# Schematic.net
KiCad netlist of a schematic drawn in Altium Designer
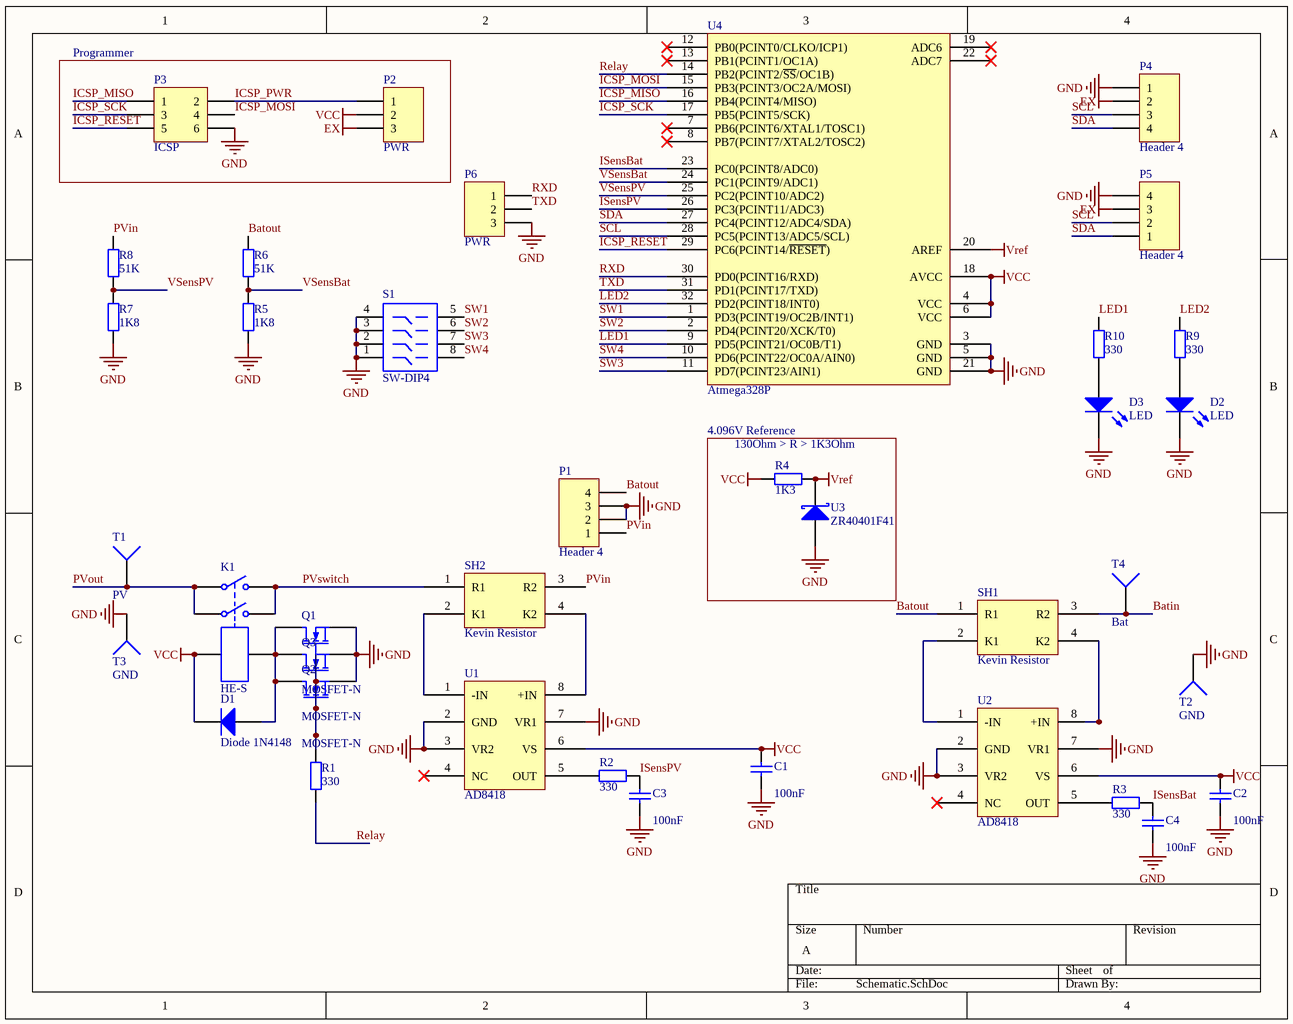
[diagram p0: Schematic.SchDoc]

(export (version "E")
  (design (tool "Eeschema 10.0.6"))
  (components
    (comp (ref "C1")
      (value "100nF")
      (footprint "CAP 0805/2012")
      (description "Capacitor")
      (fields (field (name "Comment") "Cap") (field (name "PUBLISHER") "Altium Limited"))
      (libsource (lib "Miscellaneous Devices") (part "Cap"))
    )
    (comp (ref "C2")
      (value "100nF")
      (footprint "CAP 0805/2012")
      (description "Capacitor")
      (fields (field (name "Comment") "Cap") (field (name "PUBLISHER") "Altium Limited"))
      (libsource (lib "Miscellaneous Devices") (part "Cap"))
    )
    (comp (ref "C3")
      (value "100nF")
      (footprint "CAP 0805/2012")
      (description "Capacitor")
      (fields (field (name "Comment") "Cap") (field (name "PUBLISHER") "Altium Limited"))
      (libsource (lib "Miscellaneous Devices") (part "Cap"))
    )
    (comp (ref "C4")
      (value "100nF")
      (footprint "CAP 0805/2012")
      (description "Capacitor")
      (fields (field (name "Comment") "Cap") (field (name "PUBLISHER") "Altium Limited"))
      (libsource (lib "Miscellaneous Devices") (part "Cap"))
    )
    (comp (ref "D1")
      (value "Diode 1N4148")
      (footprint "DO-35")
      (description "High Conductance Fast Diode")
      (fields (field (name "PUBLISHER") "Altium Limited"))
      (libsource (lib "Miscellaneous Devices") (part "Diode 1N4148"))
    )
    (comp (ref "D2")
      (value "LED")
      (footprint "LED 0805/2012 RED")
      (description "Typical INFRARED GaAs LED")
      (fields (field (name "PUBLISHER") "Altium Limited"))
      (libsource (lib "Miscellaneous Devices") (part "LED0"))
    )
    (comp (ref "D3")
      (value "LED")
      (footprint "LED 0805/2012 RED")
      (description "Typical INFRARED GaAs LED")
      (fields (field (name "PUBLISHER") "Altium Limited"))
      (libsource (lib "Miscellaneous Devices") (part "LED0"))
    )
    (comp (ref "K1")
      (value "HE-S")
      (footprint "Relay HE-S Parasonic")
      (description "Dual-Pole Single-Throw Relay")
      (fields (field (name "PUBLISHER") "Altium Limited"))
      (libsource (lib "Miscellaneous Devices") (part "Relay-DPST"))
    )
    (comp (ref "P1")
      (value "Header 4")
      (footprint "4Pin 6.35mm Connector")
      (description "Header, 4-Pin")
      (fields (field (name "PUBLISHER") "Altium Limited"))
      (libsource (lib "") (part "Header 4_2"))
    )
    (comp (ref "P2")
      (value "PWR")
      (footprint "HDR1X3")
      (description "Header, 3-Pin")
      (fields (field (name "PUBLISHER") "Altium Limited"))
      (libsource (lib "Miscellaneous Connectors") (part "Header 3"))
    )
    (comp (ref "P3")
      (value "ICSP")
      (footprint "HDR2X3")
      (description "Header, 3-Pin, Dual row")
      (fields (field (name "PUBLISHER") "Altium Limited"))
      (libsource (lib "Miscellaneous Connectors") (part "Header 3X2"))
    )
    (comp (ref "P4")
      (value "Header 4")
      (footprint "TE 282834-4")
      (description "Header, 4-Pin")
      (fields (field (name "PUBLISHER") "Altium Limited"))
      (libsource (lib "Miscellaneous Connectors") (part "Header 4"))
    )
    (comp (ref "P5")
      (value "Header 4")
      (footprint "TE 282834-4")
      (description "Header, 4-Pin")
      (fields (field (name "PUBLISHER") "Altium Limited"))
      (libsource (lib "") (part "Header 4_1"))
    )
    (comp (ref "P6")
      (value "PWR")
      (footprint "HDR1X3H")
      (description "Header, 3-Pin")
      (fields (field (name "PUBLISHER") "Altium Limited"))
      (libsource (lib "") (part "Header 3_1"))
    )
    (comp (ref "Q1")
      (value "MOSFET-N")
      (footprint "DIODES SOT-23-3")
      (description "N-Channel MOSFET")
      (fields (field (name "PUBLISHER") "Altium Limited"))
      (libsource (lib "Miscellaneous Devices") (part "MOSFET-N"))
    )
    (comp (ref "Q2")
      (value "MOSFET-N")
      (footprint "DIODES SOT-23-3")
      (description "N-Channel MOSFET")
      (fields (field (name "PUBLISHER") "Altium Limited"))
      (libsource (lib "Miscellaneous Devices") (part "MOSFET-N"))
    )
    (comp (ref "Q3")
      (value "MOSFET-N")
      (footprint "DIODES SOT-23-3")
      (description "N-Channel MOSFET")
      (fields (field (name "PUBLISHER") "Altium Limited"))
      (libsource (lib "Miscellaneous Devices") (part "MOSFET-N"))
    )
    (comp (ref "R1")
      (value "330")
      (footprint "RES 0805/2012")
      (description "Resistor")
      (fields (field (name "Comment") "Res2") (field (name "PUBLISHER") "Altium Limited"))
      (libsource (lib "") (part "Res2_2"))
    )
    (comp (ref "R2")
      (value "330")
      (footprint "RES 0805/2012")
      (description "Resistor")
      (fields (field (name "Comment") "Res2") (field (name "PUBLISHER") "Altium Limited"))
      (libsource (lib "Miscellaneous Devices") (part "Res2"))
    )
    (comp (ref "R3")
      (value "330")
      (footprint "RES 0805/2012")
      (description "Resistor")
      (fields (field (name "Comment") "Res2") (field (name "PUBLISHER") "Altium Limited"))
      (libsource (lib "Miscellaneous Devices") (part "Res2"))
    )
    (comp (ref "R4")
      (value "1K3")
      (footprint "RES 0805/2012")
      (description "Resistor")
      (fields (field (name "Comment") "Res2") (field (name "PUBLISHER") "Altium Limited"))
      (libsource (lib "Miscellaneous Devices") (part "Res2"))
    )
    (comp (ref "R5")
      (value "1K8")
      (footprint "RES 0805/2012")
      (description "Resistor")
      (fields (field (name "Comment") "Res2") (field (name "PUBLISHER") "Altium Limited"))
      (libsource (lib "") (part "Res2_1"))
    )
    (comp (ref "R6")
      (value "51K")
      (footprint "RES 0805/2012")
      (description "Resistor")
      (fields (field (name "Comment") "Res2") (field (name "PUBLISHER") "Altium Limited"))
      (libsource (lib "") (part "Res2_1"))
    )
    (comp (ref "R7")
      (value "1K8")
      (footprint "RES 0805/2012")
      (description "Resistor")
      (fields (field (name "Comment") "Res2") (field (name "PUBLISHER") "Altium Limited"))
      (libsource (lib "") (part "Res2_1"))
    )
    (comp (ref "R8")
      (value "51K")
      (footprint "RES 0805/2012")
      (description "Resistor")
      (fields (field (name "Comment") "Res2") (field (name "PUBLISHER") "Altium Limited"))
      (libsource (lib "") (part "Res2_1"))
    )
    (comp (ref "R9")
      (value "330")
      (footprint "RES 0805/2012")
      (description "Resistor")
      (fields (field (name "Comment") "Res2") (field (name "PUBLISHER") "Altium Limited"))
      (libsource (lib "") (part "Res2_1"))
    )
    (comp (ref "R10")
      (value "330")
      (footprint "RES 0805/2012")
      (description "Resistor")
      (fields (field (name "Comment") "Res2") (field (name "PUBLISHER") "Altium Limited"))
      (libsource (lib "") (part "Res2_1"))
    )
    (comp (ref "S1")
      (value "SW-DIP4")
      (footprint "DIP-8")
      (description "DIP Switch")
      (fields (field (name "PUBLISHER") "Altium Limited"))
      (libsource (lib "Miscellaneous Devices") (part "SW-DIP4"))
    )
    (comp (ref "SH1")
      (value "Kevin Resistor")
      (footprint "TE TLR Shunt")
      (libsource (lib "Personal Library") (part "Kevin Resistor"))
    )
    (comp (ref "SH2")
      (value "Kevin Resistor")
      (footprint "TE TLR Shunt")
      (libsource (lib "Personal Library") (part "Kevin Resistor"))
    )
    (comp (ref "T1")
      (value "PV")
      (footprint "PCB_Pin_Outsteeksel")
      (description "Socket")
      (fields (field (name "PUBLISHER") "Altium Limited"))
      (libsource (lib "Miscellaneous Connectors") (part "Socket"))
    )
    (comp (ref "T2")
      (value "GND")
      (footprint "PCB_Pin_Outsteeksel")
      (description "Socket")
      (fields (field (name "PUBLISHER") "Altium Limited"))
      (libsource (lib "Miscellaneous Connectors") (part "Socket"))
    )
    (comp (ref "T3")
      (value "GND")
      (footprint "PCB_Pin_Outsteeksel")
      (description "Socket")
      (fields (field (name "PUBLISHER") "Altium Limited"))
      (libsource (lib "Miscellaneous Connectors") (part "Socket"))
    )
    (comp (ref "T4")
      (value "Bat")
      (footprint "PCB_Pin_Outsteeksel")
      (description "Socket")
      (fields (field (name "PUBLISHER") "Altium Limited"))
      (libsource (lib "Miscellaneous Connectors") (part "Socket"))
    )
    (comp (ref "U1")
      (value "AD8418")
      (footprint "INTERSIL MSOP-8 M8.118")
      (libsource (lib "GJ24") (part "AD8418"))
    )
    (comp (ref "U2")
      (value "AD8418")
      (footprint "INTERSIL MSOP-8 M8.118")
      (libsource (lib "GJ24") (part "AD8418"))
    )
    (comp (ref "U3")
      (value "ZR40401F41")
      (footprint "DIODES SOT-23-3")
      (description "Schottky Rectifier")
      (fields (field (name "PUBLISHER") "Altium Limited"))
      (libsource (lib "Miscellaneous Devices") (part "Diode 10TQ035"))
    )
    (comp (ref "U4")
      (value "Atmega328P")
      (footprint "ST LQFP-32 7X7MM")
      (libsource (lib "GJ24") (part "Atmega328P"))
    )
  )
  (nets
    (net (code "1") (name "/Batin") (class "Default")
      (node (ref "SH1") (pin "3") (pinfunction "R2_3") (pintype "passive"))
      (node (ref "T4") (pin "1") (pinfunction "1_1") (pintype "passive"))
    )
    (net (code "2") (name "/Batout") (class "Default")
      (node (ref "P1") (pin "4") (pinfunction "4_4") (pintype "passive"))
      (node (ref "R6") (pin "2") (pinfunction "2_2") (pintype "passive"))
      (node (ref "SH1") (pin "1") (pinfunction "R1_1") (pintype "passive"))
    )
    (net (code "3") (name "/ICSP_MISO") (class "Default")
      (node (ref "P3") (pin "1") (pinfunction "1_1") (pintype "passive"))
      (node (ref "U4") (pin "16") (pinfunction "PB4(PCINT4/MISO)_16") (pintype "passive"))
    )
    (net (code "4") (name "/ICSP_MOSI") (class "Default")
      (node (ref "P3") (pin "4") (pinfunction "4_4") (pintype "passive"))
      (node (ref "U4") (pin "15") (pinfunction "PB3(PCINT3/OC2A/MOSI)_15") (pintype "passive"))
    )
    (net (code "5") (name "/ICSP_PWR") (class "Default")
      (node (ref "P2") (pin "1") (pinfunction "1_1") (pintype "passive"))
      (node (ref "P3") (pin "2") (pinfunction "2_2") (pintype "passive"))
    )
    (net (code "6") (name "/ICSP_RESET") (class "Default")
      (node (ref "P3") (pin "5") (pinfunction "5_5") (pintype "passive"))
      (node (ref "U4") (pin "29") (pinfunction "PC6(PCINT14/~{RESET})_29") (pintype "passive"))
    )
    (net (code "7") (name "/ICSP_SCK") (class "Default")
      (node (ref "P3") (pin "3") (pinfunction "3_3") (pintype "passive"))
      (node (ref "U4") (pin "17") (pinfunction "PB5(PCINT5/SCK)_17") (pintype "passive"))
    )
    (net (code "8") (name "/ISensBat") (class "Default")
      (node (ref "C4") (pin "2") (pinfunction "2_2") (pintype "passive"))
      (node (ref "R3") (pin "1") (pinfunction "1_1") (pintype "passive"))
      (node (ref "U4") (pin "23") (pinfunction "PC0(PCINT8/ADC0)_23") (pintype "passive"))
    )
    (net (code "9") (name "/ISensPV") (class "Default")
      (node (ref "C3") (pin "2") (pinfunction "2_2") (pintype "passive"))
      (node (ref "R2") (pin "1") (pinfunction "1_1") (pintype "passive"))
      (node (ref "U4") (pin "26") (pinfunction "PC3(PCINT11/ADC3)_26") (pintype "passive"))
    )
    (net (code "10") (name "/LED1") (class "Default")
      (node (ref "R10") (pin "2") (pinfunction "2_2") (pintype "passive"))
      (node (ref "U4") (pin "9") (pinfunction "PD5(PCINT21/OC0B/T1)_9") (pintype "passive"))
    )
    (net (code "11") (name "/LED2") (class "Default")
      (node (ref "R9") (pin "2") (pinfunction "2_2") (pintype "passive"))
      (node (ref "U4") (pin "32") (pinfunction "PD2(PCINT18/INT0)_32") (pintype "passive"))
    )
    (net (code "12") (name "/PVin") (class "Default")
      (node (ref "P1") (pin "1") (pinfunction "1_1") (pintype "passive"))
      (node (ref "R8") (pin "2") (pinfunction "2_2") (pintype "passive"))
      (node (ref "SH2") (pin "3") (pinfunction "R2_3") (pintype "passive"))
    )
    (net (code "13") (name "/PVout") (class "Default")
      (node (ref "K1") (pin "1") (pinfunction "1_1") (pintype "passive"))
      (node (ref "K1") (pin "3") (pinfunction "3_3") (pintype "passive"))
      (node (ref "T1") (pin "1") (pinfunction "1_1") (pintype "passive"))
    )
    (net (code "14") (name "/PVswitch") (class "Default")
      (node (ref "K1") (pin "2") (pinfunction "2_2") (pintype "passive"))
      (node (ref "K1") (pin "4") (pinfunction "4_4") (pintype "passive"))
      (node (ref "SH2") (pin "1") (pinfunction "R1_1") (pintype "passive"))
    )
    (net (code "15") (name "/RXD") (class "Default")
      (node (ref "P6") (pin "1") (pinfunction "1_1") (pintype "passive"))
      (node (ref "U4") (pin "30") (pinfunction "PD0(PCINT16/RXD)_30") (pintype "passive"))
    )
    (net (code "16") (name "/Relay") (class "Default")
      (node (ref "R1") (pin "2") (pinfunction "2_2") (pintype "passive"))
      (node (ref "U4") (pin "14") (pinfunction "PB2(PCINT2/~{SS}/OC1B)_14") (pintype "passive"))
    )
    (net (code "17") (name "/SCL") (class "Default")
      (node (ref "P4") (pin "3") (pinfunction "3_3") (pintype "passive"))
      (node (ref "P5") (pin "2") (pinfunction "2_2") (pintype "passive"))
      (node (ref "U4") (pin "28") (pinfunction "PC5(PCINT13/ADC5/SCL)_28") (pintype "passive"))
    )
    (net (code "18") (name "/SDA") (class "Default")
      (node (ref "P4") (pin "4") (pinfunction "4_4") (pintype "passive"))
      (node (ref "P5") (pin "1") (pinfunction "1_1") (pintype "passive"))
      (node (ref "U4") (pin "27") (pinfunction "PC4(PCINT12/ADC4/SDA)_27") (pintype "passive"))
    )
    (net (code "19") (name "/SW1") (class "Default")
      (node (ref "S1") (pin "5") (pinfunction "5_5") (pintype "passive"))
      (node (ref "U4") (pin "1") (pinfunction "PD3(PCINT19/OC2B/INT1)_1") (pintype "passive"))
    )
    (net (code "20") (name "/SW2") (class "Default")
      (node (ref "S1") (pin "6") (pinfunction "6_6") (pintype "passive"))
      (node (ref "U4") (pin "2") (pinfunction "PD4(PCINT20/XCK/T0)_2") (pintype "passive"))
    )
    (net (code "21") (name "/SW3") (class "Default")
      (node (ref "S1") (pin "7") (pinfunction "7_7") (pintype "passive"))
      (node (ref "U4") (pin "11") (pinfunction "PD7(PCINT23/AIN1)_11") (pintype "passive"))
    )
    (net (code "22") (name "/SW4") (class "Default")
      (node (ref "S1") (pin "8") (pinfunction "8_8") (pintype "passive"))
      (node (ref "U4") (pin "10") (pinfunction "PD6(PCINT22/OC0A/AIN0)_10") (pintype "passive"))
    )
    (net (code "23") (name "/TXD") (class "Default")
      (node (ref "P6") (pin "2") (pinfunction "2_2") (pintype "passive"))
      (node (ref "U4") (pin "31") (pinfunction "PD1(PCINT17/TXD)_31") (pintype "passive"))
    )
    (net (code "24") (name "/VSensBat") (class "Default")
      (node (ref "R5") (pin "2") (pinfunction "2_2") (pintype "passive"))
      (node (ref "R6") (pin "1") (pinfunction "1_1") (pintype "passive"))
      (node (ref "U4") (pin "24") (pinfunction "PC1(PCINT9/ADC1)_24") (pintype "passive"))
    )
    (net (code "25") (name "/VSensPV") (class "Default")
      (node (ref "R7") (pin "2") (pinfunction "2_2") (pintype "passive"))
      (node (ref "R8") (pin "1") (pinfunction "1_1") (pintype "passive"))
      (node (ref "U4") (pin "25") (pinfunction "PC2(PCINT10/ADC2)_25") (pintype "passive"))
    )
    (net (code "26") (name "EX") (class "Default")
      (node (ref "P2") (pin "3") (pinfunction "3_3") (pintype "passive"))
      (node (ref "P4") (pin "2") (pinfunction "2_2") (pintype "passive"))
      (node (ref "P5") (pin "3") (pinfunction "3_3") (pintype "passive"))
    )
    (net (code "27") (name "GND") (class "Default")
      (node (ref "C1") (pin "1") (pinfunction "1_1") (pintype "passive"))
      (node (ref "C2") (pin "1") (pinfunction "1_1") (pintype "passive"))
      (node (ref "C3") (pin "1") (pinfunction "1_1") (pintype "passive"))
      (node (ref "C4") (pin "1") (pinfunction "1_1") (pintype "passive"))
      (node (ref "D2") (pin "2") (pinfunction "K_2") (pintype "passive"))
      (node (ref "D3") (pin "2") (pinfunction "K_2") (pintype "passive"))
      (node (ref "P1") (pin "2") (pinfunction "2_2") (pintype "passive"))
      (node (ref "P1") (pin "3") (pinfunction "3_3") (pintype "passive"))
      (node (ref "P3") (pin "6") (pinfunction "6_6") (pintype "passive"))
      (node (ref "P4") (pin "1") (pinfunction "1_1") (pintype "passive"))
      (node (ref "P5") (pin "4") (pinfunction "4_4") (pintype "passive"))
      (node (ref "P6") (pin "3") (pinfunction "3_3") (pintype "passive"))
      (node (ref "Q1") (pin "2") (pinfunction "S_2") (pintype "passive"))
      (node (ref "Q2") (pin "2") (pinfunction "S_2") (pintype "passive"))
      (node (ref "Q3") (pin "2") (pinfunction "S_2") (pintype "passive"))
      (node (ref "R5") (pin "1") (pinfunction "1_1") (pintype "passive"))
      (node (ref "R7") (pin "1") (pinfunction "1_1") (pintype "passive"))
      (node (ref "S1") (pin "1") (pinfunction "1_1") (pintype "passive"))
      (node (ref "S1") (pin "2") (pinfunction "2_2") (pintype "passive"))
      (node (ref "S1") (pin "3") (pinfunction "3_3") (pintype "passive"))
      (node (ref "S1") (pin "4") (pinfunction "4_4") (pintype "passive"))
      (node (ref "T2") (pin "1") (pinfunction "1_1") (pintype "passive"))
      (node (ref "T3") (pin "1") (pinfunction "1_1") (pintype "passive"))
      (node (ref "U1") (pin "2") (pinfunction "GND_2") (pintype "passive"))
      (node (ref "U1") (pin "3") (pinfunction "VR2_3") (pintype "passive"))
      (node (ref "U1") (pin "7") (pinfunction "VR1_7") (pintype "passive"))
      (node (ref "U2") (pin "2") (pinfunction "GND_2") (pintype "passive"))
      (node (ref "U2") (pin "3") (pinfunction "VR2_3") (pintype "passive"))
      (node (ref "U2") (pin "7") (pinfunction "VR1_7") (pintype "passive"))
      (node (ref "U3") (pin "3") (pinfunction "A_3") (pintype "passive"))
      (node (ref "U4") (pin "21") (pinfunction "GND_21") (pintype "passive"))
      (node (ref "U4") (pin "3") (pinfunction "GND_3") (pintype "passive"))
      (node (ref "U4") (pin "5") (pinfunction "GND_5") (pintype "passive"))
    )
    (net (code "28") (name "Net-(D1-A)") (class "Default")
      (node (ref "D1") (pin "1") (pinfunction "A_1") (pintype "passive"))
      (node (ref "K1") (pin "6") (pinfunction "6_6") (pintype "passive"))
      (node (ref "Q1") (pin "1") (pinfunction "D_1") (pintype "passive"))
      (node (ref "Q2") (pin "1") (pinfunction "D_1") (pintype "passive"))
      (node (ref "Q3") (pin "1") (pinfunction "D_1") (pintype "passive"))
    )
    (net (code "29") (name "Net-(D2-A)") (class "Default")
      (node (ref "D2") (pin "1") (pinfunction "A_1") (pintype "passive"))
      (node (ref "R9") (pin "1") (pinfunction "1_1") (pintype "passive"))
    )
    (net (code "30") (name "Net-(D3-A)") (class "Default")
      (node (ref "D3") (pin "1") (pinfunction "A_1") (pintype "passive"))
      (node (ref "R10") (pin "1") (pinfunction "1_1") (pintype "passive"))
    )
    (net (code "31") (name "Net-(Q1-G)") (class "Default")
      (node (ref "Q1") (pin "3") (pinfunction "G_3") (pintype "passive"))
      (node (ref "Q2") (pin "3") (pinfunction "G_3") (pintype "passive"))
      (node (ref "Q3") (pin "3") (pinfunction "G_3") (pintype "passive"))
      (node (ref "R1") (pin "1") (pinfunction "1_1") (pintype "passive"))
    )
    (net (code "32") (name "Net-(SH1-K1)") (class "Default")
      (node (ref "SH1") (pin "2") (pinfunction "K1_2") (pintype "passive"))
      (node (ref "U2") (pin "1") (pinfunction "-IN_1") (pintype "passive"))
    )
    (net (code "33") (name "Net-(SH1-K2)") (class "Default")
      (node (ref "SH1") (pin "4") (pinfunction "K2_4") (pintype "passive"))
      (node (ref "U2") (pin "8") (pinfunction "+IN_8") (pintype "passive"))
    )
    (net (code "34") (name "Net-(SH2-K1)") (class "Default")
      (node (ref "SH2") (pin "2") (pinfunction "K1_2") (pintype "passive"))
      (node (ref "U1") (pin "1") (pinfunction "-IN_1") (pintype "passive"))
    )
    (net (code "35") (name "Net-(SH2-K2)") (class "Default")
      (node (ref "SH2") (pin "4") (pinfunction "K2_4") (pintype "passive"))
      (node (ref "U1") (pin "8") (pinfunction "+IN_8") (pintype "passive"))
    )
    (net (code "36") (name "Net-(U1-OUT)") (class "Default")
      (node (ref "R2") (pin "2") (pinfunction "2_2") (pintype "passive"))
      (node (ref "U1") (pin "5") (pinfunction "OUT_5") (pintype "passive"))
    )
    (net (code "37") (name "Net-(U2-OUT)") (class "Default")
      (node (ref "R3") (pin "2") (pinfunction "2_2") (pintype "passive"))
      (node (ref "U2") (pin "5") (pinfunction "OUT_5") (pintype "passive"))
    )
    (net (code "38") (name "VCC") (class "Default")
      (node (ref "C1") (pin "2") (pinfunction "2_2") (pintype "passive"))
      (node (ref "C2") (pin "2") (pinfunction "2_2") (pintype "passive"))
      (node (ref "D1") (pin "2") (pinfunction "K_2") (pintype "passive"))
      (node (ref "K1") (pin "5") (pinfunction "5_5") (pintype "passive"))
      (node (ref "P2") (pin "2") (pinfunction "2_2") (pintype "passive"))
      (node (ref "R4") (pin "2") (pinfunction "2_2") (pintype "passive"))
      (node (ref "U1") (pin "6") (pinfunction "VS_6") (pintype "passive"))
      (node (ref "U2") (pin "6") (pinfunction "VS_6") (pintype "passive"))
      (node (ref "U4") (pin "18") (pinfunction "AVCC_18") (pintype "passive"))
      (node (ref "U4") (pin "4") (pinfunction "VCC_4") (pintype "passive"))
      (node (ref "U4") (pin "6") (pinfunction "VCC_6") (pintype "passive"))
    )
    (net (code "39") (name "Vref") (class "Default")
      (node (ref "R4") (pin "1") (pinfunction "1_1") (pintype "passive"))
      (node (ref "U3") (pin "1") (pinfunction "K_1") (pintype "passive"))
      (node (ref "U4") (pin "20") (pinfunction "AREF_20") (pintype "passive"))
    )
    (net (code "40") (name "unconnected-(U1-NC-Pad4)") (class "Default")
      (node (ref "U1") (pin "4") (pinfunction "NC_4") (pintype "passive+no_connect"))
    )
    (net (code "41") (name "unconnected-(U2-NC-Pad4)") (class "Default")
      (node (ref "U2") (pin "4") (pinfunction "NC_4") (pintype "passive+no_connect"))
    )
    (net (code "42") (name "unconnected-(U4-ADC6-Pad19)") (class "Default")
      (node (ref "U4") (pin "19") (pinfunction "ADC6_19") (pintype "passive+no_connect"))
    )
    (net (code "43") (name "unconnected-(U4-ADC7-Pad22)") (class "Default")
      (node (ref "U4") (pin "22") (pinfunction "ADC7_22") (pintype "passive+no_connect"))
    )
    (net (code "44") (name "unconnected-(U4-PB0(PCINT0{slash}CLKO{slash}ICP1)-Pad12)") (class "Default")
      (node (ref "U4") (pin "12") (pinfunction "PB0(PCINT0/CLKO/ICP1)_12") (pintype "passive+no_connect"))
    )
    (net (code "45") (name "unconnected-(U4-PB1(PCINT1{slash}OC1A)-Pad13)") (class "Default")
      (node (ref "U4") (pin "13") (pinfunction "PB1(PCINT1/OC1A)_13") (pintype "passive+no_connect"))
    )
    (net (code "46") (name "unconnected-(U4-PB6(PCINT6{slash}XTAL1{slash}TOSC1)-Pad7)") (class "Default")
      (node (ref "U4") (pin "7") (pinfunction "PB6(PCINT6/XTAL1/TOSC1)_7") (pintype "passive+no_connect"))
    )
    (net (code "47") (name "unconnected-(U4-PB7(PCINT7{slash}XTAL2{slash}TOSC2)-Pad8)") (class "Default")
      (node (ref "U4") (pin "8") (pinfunction "PB7(PCINT7/XTAL2/TOSC2)_8") (pintype "passive+no_connect"))
    )
  )
)
